# MCU.net
KiCad netlist of a schematic drawn in Altium Designer
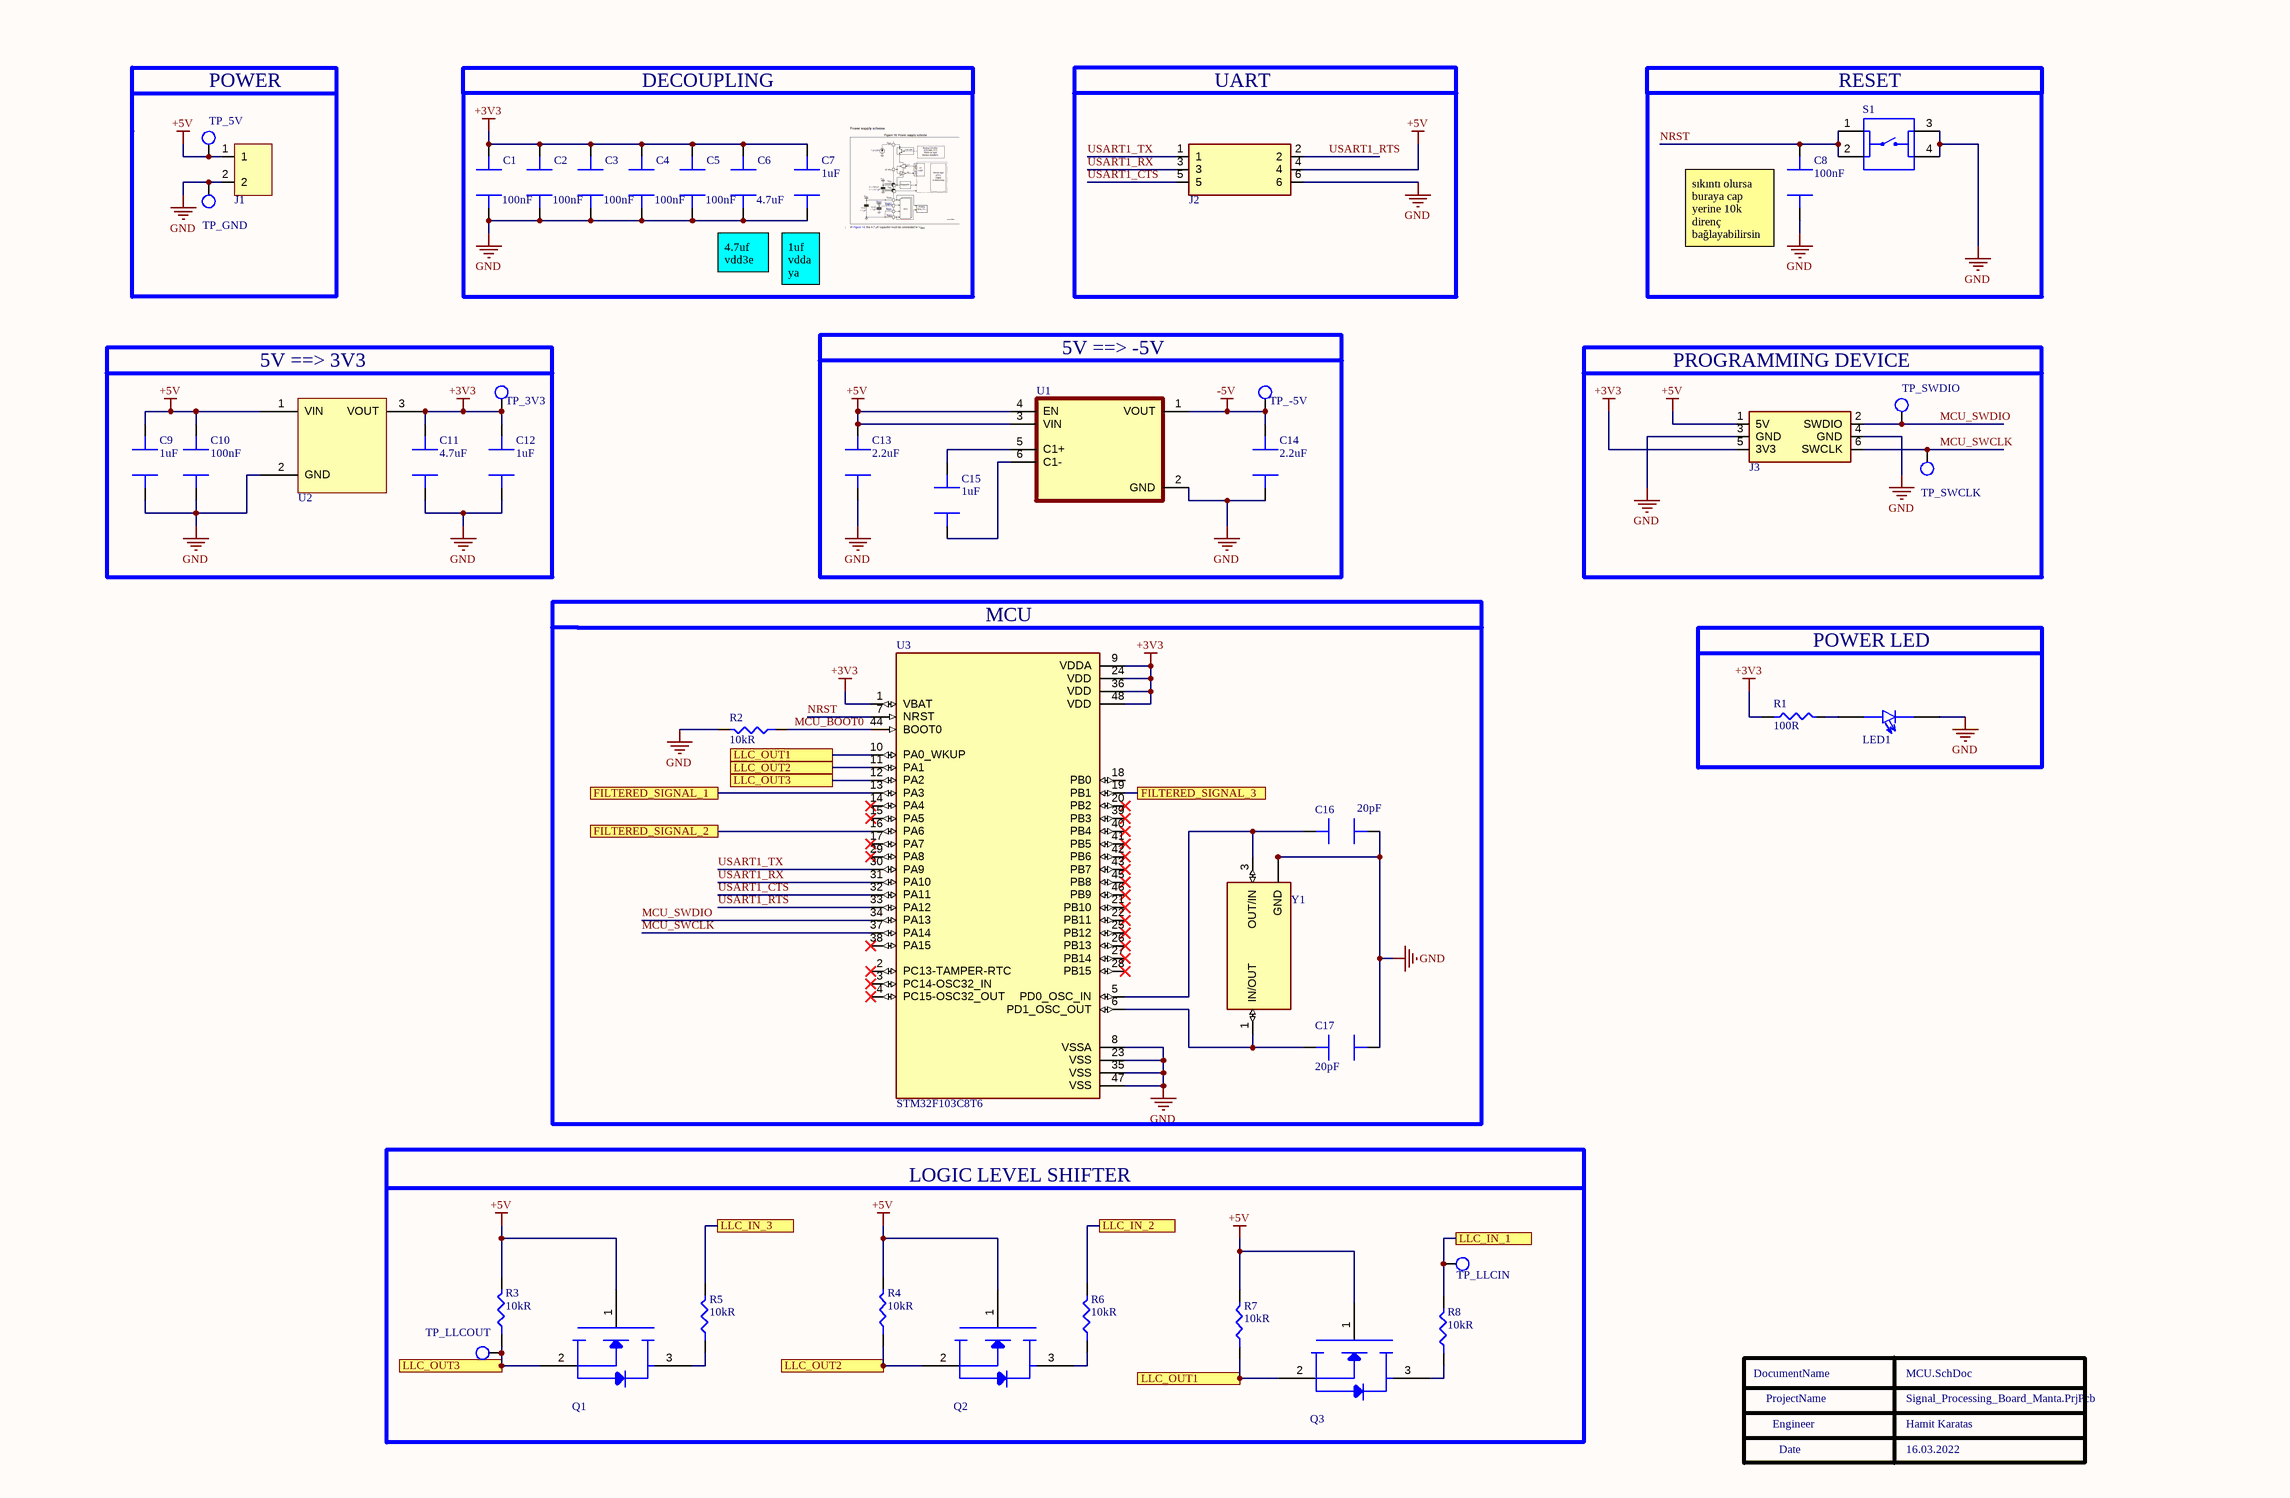
[diagram p0: MCU.SchDoc]

(export (version "E")
  (design (tool "Eeschema 10.0.6"))
  (components
    (comp (ref "C1")
      (value "CAP CER 100nF 0603")
      (footprint "CAP_0603")
      (fields
        (field (name "MANUFACTURER") "KEMET")
        (field (name "MANUFACTURER PART NUMBER") "C0603C104K5RACTU")
        (field (name "TOLERANCE") "10%")
        (field (name "CAPACITANCE") "100nF")
        (field (name "DESIGNED BY") "Hamit")
      )
      (libsource (lib "altium_giris") (part "CAP CER 100nF 0603"))
    )
    (comp (ref "C2")
      (value "CAP CER 100nF 0603")
      (footprint "CAP_0603")
      (fields
        (field (name "MANUFACTURER") "KEMET")
        (field (name "MANUFACTURER PART NUMBER") "C0603C104K5RACTU")
        (field (name "TOLERANCE") "10%")
        (field (name "CAPACITANCE") "100nF")
        (field (name "DESIGNED BY") "Hamit")
      )
      (libsource (lib "altium_giris") (part "CAP CER 100nF 0603"))
    )
    (comp (ref "C3")
      (value "CAP CER 100nF 0603")
      (footprint "CAP_0603")
      (fields
        (field (name "MANUFACTURER") "KEMET")
        (field (name "MANUFACTURER PART NUMBER") "C0603C104K5RACTU")
        (field (name "TOLERANCE") "10%")
        (field (name "CAPACITANCE") "100nF")
        (field (name "DESIGNED BY") "Hamit")
      )
      (libsource (lib "altium_giris") (part "CAP CER 100nF 0603"))
    )
    (comp (ref "C4")
      (value "CAP CER 100nF 0603")
      (footprint "CAP_0603")
      (fields
        (field (name "MANUFACTURER") "KEMET")
        (field (name "MANUFACTURER PART NUMBER") "C0603C104K5RACTU")
        (field (name "TOLERANCE") "10%")
        (field (name "CAPACITANCE") "100nF")
        (field (name "DESIGNED BY") "Hamit")
      )
      (libsource (lib "altium_giris") (part "CAP CER 100nF 0603"))
    )
    (comp (ref "C5")
      (value "CAP CER 100nF 0603")
      (footprint "CAP_0603")
      (fields
        (field (name "MANUFACTURER") "KEMET")
        (field (name "MANUFACTURER PART NUMBER") "C0603C104K5RACTU")
        (field (name "TOLERANCE") "10%")
        (field (name "CAPACITANCE") "100nF")
        (field (name "DESIGNED BY") "Hamit")
      )
      (libsource (lib "altium_giris") (part "CAP CER 100nF 0603"))
    )
    (comp (ref "C6")
      (value "CL21A475KAQNNNE")
      (footprint "cap_0805")
      (fields
        (field (name "MANUFACTURER") "Samsung")
        (field (name "TOLERANCE") "10%")
        (field (name "CAPACITANCE") "4.7uF")
        (field (name "DESIGNED BY") "Hamit")
      )
      (libsource (lib "altium_giris") (part "CAP CER 4.7 uF"))
    )
    (comp (ref "C7")
      (value "CAP CER 1uF 0805")
      (footprint "cap_0805")
      (description "0805 0.1 uF ±10 % Tolerance 50 V X7R Multilayer Ceramic Capacitors")
      (fields
        (field (name "MANUFACTURER") "Samsung")
        (field (name "MANUFACTURER PART NUMBER") "CL21B104KBFNNNE")
        (field (name "CAPACITANCE") "1uF")
        (field (name "DESIGNED BY") "Hamit")
      )
      (libsource (lib "altium_giris") (part "CAP CER 1uF 0805"))
    )
    (comp (ref "C8")
      (value "CAP CER 100nF 0603")
      (footprint "CAP_0603")
      (fields
        (field (name "MANUFACTURER") "KEMET")
        (field (name "MANUFACTURER PART NUMBER") "C0603C104K5RACTU")
        (field (name "TOLERANCE") "10%")
        (field (name "CAPACITANCE") "100nF")
        (field (name "DESIGNED BY") "Hamit")
      )
      (libsource (lib "altium_giris") (part "CAP CER 100nF 0603"))
    )
    (comp (ref "C9")
      (value "CAP CER 1uF 0805")
      (footprint "cap_0805")
      (description "0805 0.1 uF ±10 % Tolerance 50 V X7R Multilayer Ceramic Capacitors")
      (fields
        (field (name "MANUFACTURER") "Samsung")
        (field (name "MANUFACTURER PART NUMBER") "CL21B104KBFNNNE")
        (field (name "CAPACITANCE") "1uF")
        (field (name "DESIGNED BY") "Hamit")
      )
      (libsource (lib "altium_giris") (part "CAP CER 1uF 0805"))
    )
    (comp (ref "C10")
      (value "CL21B104KBCNNNC")
      (footprint "cap_0805")
      (fields
        (field (name "MANUFACTURER") "Samsung")
        (field (name "TOLERANCE") "10%")
        (field (name "VOLTAGE") "50V")
        (field (name "CAPACITANCE") "100nF")
        (field (name "DESIGNED BY") "Hamit")
      )
      (libsource (lib "altium_giris") (part "CAP cer 100nF 0805"))
    )
    (comp (ref "C11")
      (value "CL21A475KAQNNNE")
      (footprint "cap_0805")
      (fields
        (field (name "MANUFACTURER") "Samsung")
        (field (name "TOLERANCE") "10%")
        (field (name "CAPACITANCE") "4.7uF")
        (field (name "DESIGNED BY") "Hamit")
      )
      (libsource (lib "altium_giris") (part "CAP_0805_4.7uF"))
    )
    (comp (ref "C12")
      (value "CAP CER 1uF 0805")
      (footprint "cap_0805")
      (description "0805 0.1 uF ±10 % Tolerance 50 V X7R Multilayer Ceramic Capacitors")
      (fields
        (field (name "MANUFACTURER") "Samsung")
        (field (name "MANUFACTURER PART NUMBER") "CL21B104KBFNNNE")
        (field (name "CAPACITANCE") "1uF")
        (field (name "DESIGNED BY") "Hamit")
      )
      (libsource (lib "altium_giris") (part "CAP CER 1uF 0805"))
    )
    (comp (ref "C13")
      (value "CAP CER 2.2uF")
      (footprint "CAP_1206")
      (description "Cap Ceramic 2.2uF 16V X7R 10% SMD 1206 125°C Plastic T/R")
      (fields
        (field (name "MANUFACTURER") "KEMET")
        (field (name "MANUFACTURER PART NUMBER") "C1206C225K4RACTU")
        (field (name "CAPACITANCE") "2.2uF")
      )
      (libsource (lib "altium_giris") (part "CAP CER 2.2uF"))
    )
    (comp (ref "C14")
      (value "CAP CER 2.2uF")
      (footprint "CAP_1206")
      (description "Cap Ceramic 2.2uF 16V X7R 10% SMD 1206 125°C Plastic T/R")
      (fields
        (field (name "MANUFACTURER") "KEMET")
        (field (name "MANUFACTURER PART NUMBER") "C1206C225K4RACTU")
        (field (name "CAPACITANCE") "2.2uF")
      )
      (libsource (lib "altium_giris") (part "CAP CER 2.2uF"))
    )
    (comp (ref "C15")
      (value "CAP CER 1uF 0805")
      (footprint "cap_0805")
      (description "0805 0.1 uF ±10 % Tolerance 50 V X7R Multilayer Ceramic Capacitors")
      (fields
        (field (name "MANUFACTURER") "Samsung")
        (field (name "MANUFACTURER PART NUMBER") "CL21B104KBFNNNE")
        (field (name "CAPACITANCE") "1uF")
        (field (name "DESIGNED BY") "Hamit")
      )
      (libsource (lib "altium_giris") (part "CAP CER 1uF 0805"))
    )
    (comp (ref "C16")
      (value "CL10C200JB8NNNC")
      (footprint "CAP_0603")
      (fields
        (field (name "MANUFACTURER") "Samsung")
        (field (name "TOLERANCE") "5%")
        (field (name "VOLTAGE") "50V")
        (field (name "CAPACITANCE") "20pF")
        (field (name "DESIGNED BY") "Hamit")
      )
      (libsource (lib "altium_giris") (part "CAP CER 20PF"))
    )
    (comp (ref "C17")
      (value "CL10C200JB8NNNC")
      (footprint "CAP_0603")
      (fields
        (field (name "MANUFACTURER") "Samsung")
        (field (name "TOLERANCE") "5%")
        (field (name "VOLTAGE") "50V")
        (field (name "CAPACITANCE") "20pF")
        (field (name "DESIGNED BY") "Hamit")
      )
      (libsource (lib "altium_giris") (part "CAP CER 20PF"))
    )
    (comp (ref "J1")
      (value "TERMINAL BLOCK, PLUGGABLE, 5.08,")
      (footprint "TBP01R1-508-02BE")
      (description "Conn Shrouded Header HDR 2 POS 5.08mm Solder RA Side Entry Thru-Hole Bag")
      (fields
        (field (name "MANUFACTURER") "CUI")
        (field (name "MANUFACTURER PART NUMBER") "TBP01R1-508-02BE")
        (field (name "DESIGNED BY") "Hamit")
      )
      (libsource (lib "altium_giris") (part "TERMINAL BLOCK TBP01R1-508-02BE"))
    )
    (comp (ref "J2")
      (value "67997-206HLF")
      (footprint "CONN 6 PINS 2 ROWS")
      (description "Conn Unshrouded Header HDR 6 POS 2.54mm Solder ST Top Entry Thru-Hole BergStik® Bulk")
      (fields (field (name "MANUFACTURER") "ICC"))
      (libsource (lib "altium_giris") (part "CONN 6 PIN 2 ROWS"))
    )
    (comp (ref "J3")
      (value "67997-206HLF")
      (footprint "CONN 6 PINS 2 ROWS")
      (description "Conn Unshrouded Header HDR 6 POS 2.54mm Solder ST Top Entry Thru-Hole BergStik® Bulk")
      (fields (field (name "MANUFACTURER") "ICC"))
      (libsource (lib "altium_giris") (part "CONN 6 PIN 2 ROWS"))
    )
    (comp (ref "LED1")
      (value "LTST-C171GKT")
      (footprint "LED GREEN 0805")
      (description "Green 0805 130 º Min 5 mcd Typical 12 mcd Water Clear Lens SMT LED")
      (fields (field (name "MANUFACTURER") "Vishay Lite-On") (field (name "DESIGNED BY") "Hamit"))
      (libsource (lib "altium_giris") (part "LED GREEN 0805"))
    )
    (comp (ref "Q1")
      (value "MOSFET 2N7002W")
      (footprint "SOT-323")
      (description "MOSFETs (Field Effect Transistor), SOT-323, 60V, 0.115A, N, 0.200W")
      (fields
        (field (name "MANUFACTURER") "ON Semiconductor / Fairchild")
        (field (name "MANUFACTURER PART NUMBER") "2N7002W")
      )
      (libsource (lib "altium_giris") (part "MOSFET 2N7002W"))
    )
    (comp (ref "Q2")
      (value "MOSFET 2N7002W")
      (footprint "SOT-323")
      (description "MOSFETs (Field Effect Transistor), SOT-323, 60V, 0.115A, N, 0.200W")
      (fields
        (field (name "MANUFACTURER") "ON Semiconductor / Fairchild")
        (field (name "MANUFACTURER PART NUMBER") "2N7002W")
      )
      (libsource (lib "altium_giris") (part "MOSFET 2N7002W"))
    )
    (comp (ref "Q3")
      (value "MOSFET 2N7002W")
      (footprint "SOT-323")
      (description "MOSFETs (Field Effect Transistor), SOT-323, 60V, 0.115A, N, 0.200W")
      (fields
        (field (name "MANUFACTURER") "ON Semiconductor / Fairchild")
        (field (name "MANUFACTURER PART NUMBER") "2N7002W")
      )
      (libsource (lib "altium_giris") (part "MOSFET 2N7002W"))
    )
    (comp (ref "R1")
      (value "RC0603FR-7W100RL")
      (footprint "RES_0603")
      (description "RESISTOR, 0603, 100R, 1%")
      (fields
        (field (name "MANUFACTURER") "Yageo")
        (field (name "TOLERANCE") "1%")
        (field (name "RESISTANCE") "100R")
      )
      (libsource (lib "altium_giris") (part "RES 100 OHM 0603"))
    )
    (comp (ref "R2")
      (value "RES 10K OHM 0603")
      (footprint "RES_0603")
      (description "Res General Purpose Thick Film 0603 10K Ohm 1% 1/10W ±100ppm/°C Molded SMD Paper T/R")
      (fields
        (field (name "MANUFACTURER") "Yageo")
        (field (name "MANUFACTURER PART NUMBER") "RC0603FR-0710KL")
        (field (name "RESISTANCE") "10kR")
        (field (name "DESIGNED BY") "Hamit")
      )
      (libsource (lib "altium_giris") (part "RES 10K OHM 0603"))
    )
    (comp (ref "R3")
      (value "RES 10K OHM 0603")
      (footprint "RES_0603")
      (description "Res General Purpose Thick Film 0603 10K Ohm 1% 1/10W ±100ppm/°C Molded SMD Paper T/R")
      (fields
        (field (name "MANUFACTURER") "Yageo")
        (field (name "MANUFACTURER PART NUMBER") "RC0603FR-0710KL")
        (field (name "RESISTANCE") "10kR")
        (field (name "DESIGNED BY") "Hamit")
      )
      (libsource (lib "altium_giris") (part "RES 10K OHM 0603"))
    )
    (comp (ref "R4")
      (value "RES 10K OHM 0603")
      (footprint "RES_0603")
      (description "Res General Purpose Thick Film 0603 10K Ohm 1% 1/10W ±100ppm/°C Molded SMD Paper T/R")
      (fields
        (field (name "MANUFACTURER") "Yageo")
        (field (name "MANUFACTURER PART NUMBER") "RC0603FR-0710KL")
        (field (name "RESISTANCE") "10kR")
        (field (name "DESIGNED BY") "Hamit")
      )
      (libsource (lib "altium_giris") (part "RES 10K OHM 0603"))
    )
    (comp (ref "R5")
      (value "RES 10K OHM 0603")
      (footprint "RES_0603")
      (description "Res General Purpose Thick Film 0603 10K Ohm 1% 1/10W ±100ppm/°C Molded SMD Paper T/R")
      (fields
        (field (name "MANUFACTURER") "Yageo")
        (field (name "MANUFACTURER PART NUMBER") "RC0603FR-0710KL")
        (field (name "RESISTANCE") "10kR")
        (field (name "DESIGNED BY") "Hamit")
      )
      (libsource (lib "altium_giris") (part "RES 10K OHM 0603"))
    )
    (comp (ref "R6")
      (value "RES 10K OHM 0603")
      (footprint "RES_0603")
      (description "Res General Purpose Thick Film 0603 10K Ohm 1% 1/10W ±100ppm/°C Molded SMD Paper T/R")
      (fields
        (field (name "MANUFACTURER") "Yageo")
        (field (name "MANUFACTURER PART NUMBER") "RC0603FR-0710KL")
        (field (name "RESISTANCE") "10kR")
        (field (name "DESIGNED BY") "Hamit")
      )
      (libsource (lib "altium_giris") (part "RES 10K OHM 0603"))
    )
    (comp (ref "R7")
      (value "RES 10K OHM 0603")
      (footprint "RES_0603")
      (description "Res General Purpose Thick Film 0603 10K Ohm 1% 1/10W ±100ppm/°C Molded SMD Paper T/R")
      (fields
        (field (name "MANUFACTURER") "Yageo")
        (field (name "MANUFACTURER PART NUMBER") "RC0603FR-0710KL")
        (field (name "RESISTANCE") "10kR")
        (field (name "DESIGNED BY") "Hamit")
      )
      (libsource (lib "altium_giris") (part "RES 10K OHM 0603"))
    )
    (comp (ref "R8")
      (value "RES 10K OHM 0603")
      (footprint "RES_0603")
      (description "Res General Purpose Thick Film 0603 10K Ohm 1% 1/10W ±100ppm/°C Molded SMD Paper T/R")
      (fields
        (field (name "MANUFACTURER") "Yageo")
        (field (name "MANUFACTURER PART NUMBER") "RC0603FR-0710KL")
        (field (name "RESISTANCE") "10kR")
        (field (name "DESIGNED BY") "Hamit")
      )
      (libsource (lib "altium_giris") (part "RES 10K OHM 0603"))
    )
    (comp (ref "S1")
      (value "1825910-6")
      (footprint "button")
      (description "Switch Tactile OFF (ON) SPST Round Button PC Pins 0.05A 24VDC 1.57N Thru-Hole Loose")
      (fields (field (name "MANUFACTURER") "TE Connectivity Alcoswitch"))
      (libsource (lib "altium_giris") (part "button 4 pads"))
    )
    (comp (ref "TP_-5V")
      (value "TEST_POINT")
      (footprint "TEST POINT")
      (libsource (lib "altium_giris") (part "TEST POINT"))
    )
    (comp (ref "TP_3V3")
      (value "TEST_POINT")
      (footprint "TEST POINT")
      (libsource (lib "altium_giris") (part "TEST POINT"))
    )
    (comp (ref "TP_5V")
      (value "TEST_POINT")
      (footprint "TEST POINT")
      (libsource (lib "altium_giris") (part "TEST POINT"))
    )
    (comp (ref "TP_GND")
      (value "TEST_POINT")
      (footprint "TEST POINT")
      (libsource (lib "altium_giris") (part "TEST POINT"))
    )
    (comp (ref "TP_LLCIN")
      (value "TEST_POINT")
      (footprint "TEST POINT")
      (libsource (lib "altium_giris") (part "TEST POINT"))
    )
    (comp (ref "TP_LLCOUT")
      (value "TEST_POINT")
      (footprint "TEST POINT")
      (libsource (lib "altium_giris") (part "TEST POINT"))
    )
    (comp (ref "TP_SWCLK")
      (value "TEST_POINT")
      (footprint "TEST POINT")
      (libsource (lib "altium_giris") (part "TEST POINT"))
    )
    (comp (ref "TP_SWDIO")
      (value "TEST_POINT")
      (footprint "TEST POINT")
      (libsource (lib "altium_giris") (part "TEST POINT"))
    )
    (comp (ref "U1")
      (value "Voltage Regulator (5V -> -5V) LM2776DBVT")
      (footprint "SOT23-6")
      (description "Charge Pump INV -2.7V to -5.5V 200mA 6-Pin SOT-23 T/R")
      (fields
        (field (name "MANUFACTURER") "Texas Instruments")
        (field (name "MANUFACTURER PART NUMBER") "LM2776DBVT")
      )
      (libsource (lib "altium_giris") (part "Voltage Regulator (5V -{gt} -5V) LM2776DBVT"))
    )
    (comp (ref "U2")
      (value "AP7361-33E-13")
      (footprint "AP7361-33E-13")
      (description "LDO Regulator Pos 3.3V 1A 4-Pin(3+Tab) SOT-223 T/R")
      (fields (field (name "MANUFACTURER") "Diodes") (field (name "DESIGNED BY") "Hamit"))
      (libsource (lib "altium_giris") (part "REGULATOR AP7361-33E-13"))
    )
    (comp (ref "U3")
      (value "STM32F103C8T6")
      (footprint "LQFP-48")
      (description "IC MCU 32BIT 64KB FLASH 48LQFP")
      (fields (field (name "MANUFACTURER") "STMicroelectronics"))
      (libsource (lib "altium_giris") (part "STM32F103C8T6"))
    )
    (comp (ref "Y1")
      (value "CRYSTAL 8MHZ")
      (footprint "CRYSTAL 8MHZ")
      (description "Crystal 8MHz ±20ppm (Tol) ±30ppm (Stability) 12pF FUND 400Ohm 4-Pin Mini-CSMD T/R")
      (fields
        (field (name "MANUFACTURER") "ECS International")
        (field (name "MANUFACTURER PART NUMBER") "ECS-80-12-33-JGN-TR")
      )
      (libsource (lib "altium_giris") (part "CRYSTAL 8MHZ"))
    )
  )
  (nets
    (net (code "1") (name "+3V3") (class "Default")
      (node (ref "C1") (pin "2") (pinfunction "2_2") (pintype "passive"))
      (node (ref "C11") (pin "2") (pinfunction "2_2") (pintype "passive"))
      (node (ref "C12") (pin "2") (pinfunction "2_2") (pintype "passive"))
      (node (ref "C2") (pin "2") (pinfunction "2_2") (pintype "passive"))
      (node (ref "C3") (pin "2") (pinfunction "2_2") (pintype "passive"))
      (node (ref "C4") (pin "2") (pinfunction "2_2") (pintype "passive"))
      (node (ref "C5") (pin "2") (pinfunction "2_2") (pintype "passive"))
      (node (ref "C6") (pin "2") (pinfunction "2_2") (pintype "passive"))
      (node (ref "C7") (pin "2") (pinfunction "2_2") (pintype "passive"))
      (node (ref "J3") (pin "5") (pinfunction "5_5") (pintype "passive"))
      (node (ref "R1") (pin "2") (pinfunction "2_2") (pintype "passive"))
      (node (ref "TP_3V3") (pin "1") (pinfunction "TP_1") (pintype "passive"))
      (node (ref "U2") (pin "3") (pinfunction "VOUT_3") (pintype "passive"))
      (node (ref "U3") (pin "1") (pinfunction "VBAT_1") (pintype "bidirectional"))
      (node (ref "U3") (pin "24") (pinfunction "VDD_24") (pintype "power_in"))
      (node (ref "U3") (pin "36") (pinfunction "VDD_36") (pintype "power_in"))
      (node (ref "U3") (pin "48") (pinfunction "VDD_48") (pintype "power_in"))
      (node (ref "U3") (pin "9") (pinfunction "VDDA_9") (pintype "power_in"))
    )
    (net (code "2") (name "+5V") (class "Default")
      (node (ref "C10") (pin "2") (pinfunction "2_2") (pintype "passive"))
      (node (ref "C13") (pin "2") (pinfunction "2_2") (pintype "passive"))
      (node (ref "C9") (pin "2") (pinfunction "2_2") (pintype "passive"))
      (node (ref "J1") (pin "1") (pinfunction "1_1") (pintype "power_in"))
      (node (ref "J2") (pin "4") (pinfunction "4_4") (pintype "passive"))
      (node (ref "J3") (pin "1") (pinfunction "1_1") (pintype "passive"))
      (node (ref "Q1") (pin "1") (pinfunction "G_1") (pintype "passive"))
      (node (ref "Q2") (pin "1") (pinfunction "G_1") (pintype "passive"))
      (node (ref "Q3") (pin "1") (pinfunction "G_1") (pintype "passive"))
      (node (ref "R3") (pin "2") (pinfunction "2_2") (pintype "passive"))
      (node (ref "R4") (pin "2") (pinfunction "2_2") (pintype "passive"))
      (node (ref "R7") (pin "2") (pinfunction "2_2") (pintype "passive"))
      (node (ref "TP_5V") (pin "1") (pinfunction "TP_1") (pintype "passive"))
      (node (ref "U1") (pin "3") (pinfunction "VIN_3") (pintype "passive"))
      (node (ref "U1") (pin "4") (pinfunction "EN_4") (pintype "passive"))
      (node (ref "U2") (pin "1") (pinfunction "VIN_1") (pintype "passive"))
    )
    (net (code "3") (name "-5V") (class "Default")
      (node (ref "C14") (pin "2") (pinfunction "2_2") (pintype "passive"))
      (node (ref "TP_-5V") (pin "1") (pinfunction "TP_1") (pintype "passive"))
      (node (ref "U1") (pin "1") (pinfunction "VOUT_1") (pintype "passive"))
    )
    (net (code "4") (name "/FILTERED_SIGNAL_1") (class "Default")
      (node (ref "U3") (pin "13") (pinfunction "PA3_13") (pintype "bidirectional"))
    )
    (net (code "5") (name "/FILTERED_SIGNAL_2") (class "Default")
      (node (ref "U3") (pin "16") (pinfunction "PA6_16") (pintype "bidirectional"))
    )
    (net (code "6") (name "/FILTERED_SIGNAL_3") (class "Default")
      (node (ref "U3") (pin "19") (pinfunction "PB1_19") (pintype "bidirectional"))
    )
    (net (code "7") (name "/LLC_IN_1") (class "Default")
      (node (ref "R8") (pin "2") (pinfunction "2_2") (pintype "passive"))
      (node (ref "TP_LLCIN") (pin "1") (pinfunction "TP_1") (pintype "passive"))
    )
    (net (code "8") (name "/LLC_IN_2") (class "Default")
      (node (ref "R6") (pin "2") (pinfunction "2_2") (pintype "passive"))
    )
    (net (code "9") (name "/LLC_IN_3") (class "Default")
      (node (ref "R5") (pin "2") (pinfunction "2_2") (pintype "passive"))
    )
    (net (code "10") (name "/LLC_OUT1") (class "Default")
      (node (ref "Q3") (pin "2") (pinfunction "S_2") (pintype "passive"))
      (node (ref "R7") (pin "1") (pinfunction "1_1") (pintype "passive"))
      (node (ref "U3") (pin "10") (pinfunction "PA0_WKUP_10") (pintype "bidirectional"))
    )
    (net (code "11") (name "/LLC_OUT2") (class "Default")
      (node (ref "Q2") (pin "2") (pinfunction "S_2") (pintype "passive"))
      (node (ref "R4") (pin "1") (pinfunction "1_1") (pintype "passive"))
      (node (ref "U3") (pin "11") (pinfunction "PA1_11") (pintype "bidirectional"))
    )
    (net (code "12") (name "/LLC_OUT3") (class "Default")
      (node (ref "Q1") (pin "2") (pinfunction "S_2") (pintype "passive"))
      (node (ref "R3") (pin "1") (pinfunction "1_1") (pintype "passive"))
      (node (ref "TP_LLCOUT") (pin "1") (pinfunction "TP_1") (pintype "passive"))
      (node (ref "U3") (pin "12") (pinfunction "PA2_12") (pintype "bidirectional"))
    )
    (net (code "13") (name "/MCU_BOOT0") (class "Default")
      (node (ref "R2") (pin "1") (pinfunction "1_1") (pintype "passive"))
      (node (ref "U3") (pin "44") (pinfunction "BOOT0_44") (pintype "input"))
    )
    (net (code "14") (name "/MCU_SWCLK") (class "Default")
      (node (ref "J3") (pin "6") (pinfunction "6_6") (pintype "passive"))
      (node (ref "TP_SWCLK") (pin "1") (pinfunction "TP_1") (pintype "passive"))
      (node (ref "U3") (pin "37") (pinfunction "PA14_37") (pintype "bidirectional"))
    )
    (net (code "15") (name "/MCU_SWDIO") (class "Default")
      (node (ref "J3") (pin "2") (pinfunction "2_2") (pintype "passive"))
      (node (ref "TP_SWDIO") (pin "1") (pinfunction "TP_1") (pintype "passive"))
      (node (ref "U3") (pin "34") (pinfunction "PA13_34") (pintype "bidirectional"))
    )
    (net (code "16") (name "/NRST") (class "Default")
      (node (ref "C8") (pin "2") (pinfunction "2_2") (pintype "passive"))
      (node (ref "S1") (pin "1") (pinfunction "1_1") (pintype "passive"))
      (node (ref "S1") (pin "2") (pinfunction "2_2") (pintype "passive"))
      (node (ref "U3") (pin "7") (pinfunction "NRST_7") (pintype "input"))
    )
    (net (code "17") (name "/USART1_CTS") (class "Default")
      (node (ref "J2") (pin "5") (pinfunction "5_5") (pintype "passive"))
      (node (ref "U3") (pin "32") (pinfunction "PA11_32") (pintype "bidirectional"))
    )
    (net (code "18") (name "/USART1_RTS") (class "Default")
      (node (ref "J2") (pin "2") (pinfunction "2_2") (pintype "passive"))
      (node (ref "U3") (pin "33") (pinfunction "PA12_33") (pintype "bidirectional"))
    )
    (net (code "19") (name "/USART1_RX") (class "Default")
      (node (ref "J2") (pin "3") (pinfunction "3_3") (pintype "passive"))
      (node (ref "U3") (pin "31") (pinfunction "PA10_31") (pintype "bidirectional"))
    )
    (net (code "20") (name "/USART1_TX") (class "Default")
      (node (ref "J2") (pin "1") (pinfunction "1_1") (pintype "passive"))
      (node (ref "U3") (pin "30") (pinfunction "PA9_30") (pintype "bidirectional"))
    )
    (net (code "21") (name "GND") (class "Default")
      (node (ref "C1") (pin "1") (pinfunction "1_1") (pintype "passive"))
      (node (ref "C10") (pin "1") (pinfunction "1_1") (pintype "passive"))
      (node (ref "C11") (pin "1") (pinfunction "1_1") (pintype "passive"))
      (node (ref "C12") (pin "1") (pinfunction "1_1") (pintype "passive"))
      (node (ref "C13") (pin "1") (pinfunction "1_1") (pintype "passive"))
      (node (ref "C14") (pin "1") (pinfunction "1_1") (pintype "passive"))
      (node (ref "C16") (pin "1") (pinfunction "1_1") (pintype "passive"))
      (node (ref "C17") (pin "1") (pinfunction "1_1") (pintype "passive"))
      (node (ref "C2") (pin "1") (pinfunction "1_1") (pintype "passive"))
      (node (ref "C3") (pin "1") (pinfunction "1_1") (pintype "passive"))
      (node (ref "C4") (pin "1") (pinfunction "1_1") (pintype "passive"))
      (node (ref "C5") (pin "1") (pinfunction "1_1") (pintype "passive"))
      (node (ref "C6") (pin "1") (pinfunction "1_1") (pintype "passive"))
      (node (ref "C7") (pin "1") (pinfunction "1_1") (pintype "passive"))
      (node (ref "C8") (pin "1") (pinfunction "1_1") (pintype "passive"))
      (node (ref "C9") (pin "1") (pinfunction "1_1") (pintype "passive"))
      (node (ref "J1") (pin "2") (pinfunction "2_2") (pintype "power_in"))
      (node (ref "J2") (pin "6") (pinfunction "6_6") (pintype "passive"))
      (node (ref "J3") (pin "3") (pinfunction "3_3") (pintype "passive"))
      (node (ref "J3") (pin "4") (pinfunction "4_4") (pintype "passive"))
      (node (ref "LED1") (pin "C") (pinfunction "C_C") (pintype "passive"))
      (node (ref "R2") (pin "2") (pinfunction "2_2") (pintype "passive"))
      (node (ref "S1") (pin "3") (pinfunction "3_3") (pintype "passive"))
      (node (ref "S1") (pin "4") (pinfunction "4_4") (pintype "passive"))
      (node (ref "TP_GND") (pin "1") (pinfunction "TP_1") (pintype "passive"))
      (node (ref "U1") (pin "2") (pinfunction "GND_2") (pintype "power_in"))
      (node (ref "U2") (pin "2") (pinfunction "GND_2") (pintype "passive"))
      (node (ref "U3") (pin "23") (pinfunction "VSS_23") (pintype "power_in"))
      (node (ref "U3") (pin "35") (pinfunction "VSS_35") (pintype "power_in"))
      (node (ref "U3") (pin "47") (pinfunction "VSS_47") (pintype "power_in"))
      (node (ref "U3") (pin "8") (pinfunction "VSSA_8") (pintype "power_in"))
      (node (ref "Y1") (pin "2") (pinfunction "GND_2") (pintype "power_in"))
      (node (ref "Y1") (pin "4") (pinfunction "GND_4") (pintype "power_in"))
    )
    (net (code "22") (name "Net-(LED1-PadA)") (class "Default")
      (node (ref "LED1") (pin "A") (pinfunction "A_A") (pintype "passive"))
      (node (ref "R1") (pin "1") (pinfunction "1_1") (pintype "passive"))
    )
    (net (code "23") (name "Net-(Q1-D)") (class "Default")
      (node (ref "Q1") (pin "3") (pinfunction "D_3") (pintype "passive"))
      (node (ref "R5") (pin "1") (pinfunction "1_1") (pintype "passive"))
    )
    (net (code "24") (name "Net-(Q2-D)") (class "Default")
      (node (ref "Q2") (pin "3") (pinfunction "D_3") (pintype "passive"))
      (node (ref "R6") (pin "1") (pinfunction "1_1") (pintype "passive"))
    )
    (net (code "25") (name "Net-(Q3-D)") (class "Default")
      (node (ref "Q3") (pin "3") (pinfunction "D_3") (pintype "passive"))
      (node (ref "R8") (pin "1") (pinfunction "1_1") (pintype "passive"))
    )
    (net (code "26") (name "Net-(U1-C1+)") (class "Default")
      (node (ref "C15") (pin "2") (pinfunction "2_2") (pintype "passive"))
      (node (ref "U1") (pin "5") (pinfunction "C1+_5") (pintype "passive"))
    )
    (net (code "27") (name "Net-(U1-C1-)") (class "Default")
      (node (ref "C15") (pin "1") (pinfunction "1_1") (pintype "passive"))
      (node (ref "U1") (pin "6") (pinfunction "C1-_6") (pintype "passive"))
    )
    (net (code "28") (name "Net-(U3-PD0_OSC_IN)") (class "Default")
      (node (ref "C16") (pin "2") (pinfunction "2_2") (pintype "passive"))
      (node (ref "U3") (pin "5") (pinfunction "PD0_OSC_IN_5") (pintype "bidirectional"))
      (node (ref "Y1") (pin "3") (pinfunction "OUT/IN_3") (pintype "bidirectional"))
    )
    (net (code "29") (name "Net-(U3-PD1_OSC_OUT)") (class "Default")
      (node (ref "C17") (pin "2") (pinfunction "2_2") (pintype "passive"))
      (node (ref "U3") (pin "6") (pinfunction "PD1_OSC_OUT_6") (pintype "bidirectional"))
      (node (ref "Y1") (pin "1") (pinfunction "IN/OUT_1") (pintype "bidirectional"))
    )
    (net (code "30") (name "unconnected-(U3-PA4-Pad14)") (class "Default")
      (node (ref "U3") (pin "14") (pinfunction "PA4_14") (pintype "bidirectional+no_connect"))
    )
    (net (code "31") (name "unconnected-(U3-PA5-Pad15)") (class "Default")
      (node (ref "U3") (pin "15") (pinfunction "PA5_15") (pintype "bidirectional+no_connect"))
    )
    (net (code "32") (name "unconnected-(U3-PA7-Pad17)") (class "Default")
      (node (ref "U3") (pin "17") (pinfunction "PA7_17") (pintype "bidirectional+no_connect"))
    )
    (net (code "33") (name "unconnected-(U3-PA8-Pad29)") (class "Default")
      (node (ref "U3") (pin "29") (pinfunction "PA8_29") (pintype "bidirectional+no_connect"))
    )
    (net (code "34") (name "unconnected-(U3-PA15-Pad38)") (class "Default")
      (node (ref "U3") (pin "38") (pinfunction "PA15_38") (pintype "bidirectional+no_connect"))
    )
    (net (code "35") (name "unconnected-(U3-PB0-Pad18)") (class "Default")
      (node (ref "U3") (pin "18") (pinfunction "PB0_18") (pintype "bidirectional"))
    )
    (net (code "36") (name "unconnected-(U3-PB2-Pad20)") (class "Default")
      (node (ref "U3") (pin "20") (pinfunction "PB2_20") (pintype "bidirectional+no_connect"))
    )
    (net (code "37") (name "unconnected-(U3-PB3-Pad39)") (class "Default")
      (node (ref "U3") (pin "39") (pinfunction "PB3_39") (pintype "bidirectional+no_connect"))
    )
    (net (code "38") (name "unconnected-(U3-PB4-Pad40)") (class "Default")
      (node (ref "U3") (pin "40") (pinfunction "PB4_40") (pintype "bidirectional+no_connect"))
    )
    (net (code "39") (name "unconnected-(U3-PB5-Pad41)") (class "Default")
      (node (ref "U3") (pin "41") (pinfunction "PB5_41") (pintype "bidirectional+no_connect"))
    )
    (net (code "40") (name "unconnected-(U3-PB6-Pad42)") (class "Default")
      (node (ref "U3") (pin "42") (pinfunction "PB6_42") (pintype "bidirectional+no_connect"))
    )
    (net (code "41") (name "unconnected-(U3-PB7-Pad43)") (class "Default")
      (node (ref "U3") (pin "43") (pinfunction "PB7_43") (pintype "bidirectional+no_connect"))
    )
    (net (code "42") (name "unconnected-(U3-PB8-Pad45)") (class "Default")
      (node (ref "U3") (pin "45") (pinfunction "PB8_45") (pintype "bidirectional+no_connect"))
    )
    (net (code "43") (name "unconnected-(U3-PB9-Pad46)") (class "Default")
      (node (ref "U3") (pin "46") (pinfunction "PB9_46") (pintype "bidirectional+no_connect"))
    )
    (net (code "44") (name "unconnected-(U3-PB10-Pad21)") (class "Default")
      (node (ref "U3") (pin "21") (pinfunction "PB10_21") (pintype "bidirectional+no_connect"))
    )
    (net (code "45") (name "unconnected-(U3-PB11-Pad22)") (class "Default")
      (node (ref "U3") (pin "22") (pinfunction "PB11_22") (pintype "bidirectional+no_connect"))
    )
    (net (code "46") (name "unconnected-(U3-PB12-Pad25)") (class "Default")
      (node (ref "U3") (pin "25") (pinfunction "PB12_25") (pintype "bidirectional+no_connect"))
    )
    (net (code "47") (name "unconnected-(U3-PB13-Pad26)") (class "Default")
      (node (ref "U3") (pin "26") (pinfunction "PB13_26") (pintype "bidirectional+no_connect"))
    )
    (net (code "48") (name "unconnected-(U3-PB14-Pad27)") (class "Default")
      (node (ref "U3") (pin "27") (pinfunction "PB14_27") (pintype "bidirectional+no_connect"))
    )
    (net (code "49") (name "unconnected-(U3-PB15-Pad28)") (class "Default")
      (node (ref "U3") (pin "28") (pinfunction "PB15_28") (pintype "bidirectional+no_connect"))
    )
    (net (code "50") (name "unconnected-(U3-PC13-TAMPER-RTC-Pad2)") (class "Default")
      (node (ref "U3") (pin "2") (pinfunction "PC13-TAMPER-RTC_2") (pintype "bidirectional+no_connect"))
    )
    (net (code "51") (name "unconnected-(U3-PC14-OSC32_IN-Pad3)") (class "Default")
      (node (ref "U3") (pin "3") (pinfunction "PC14-OSC32_IN_3") (pintype "bidirectional+no_connect"))
    )
    (net (code "52") (name "unconnected-(U3-PC15-OSC32_OUT-Pad4)") (class "Default")
      (node (ref "U3") (pin "4") (pinfunction "PC15-OSC32_OUT_4") (pintype "bidirectional+no_connect"))
    )
  )
)
